# esp_garden.net
KiCad netlist of a schematic drawn in EAGLE
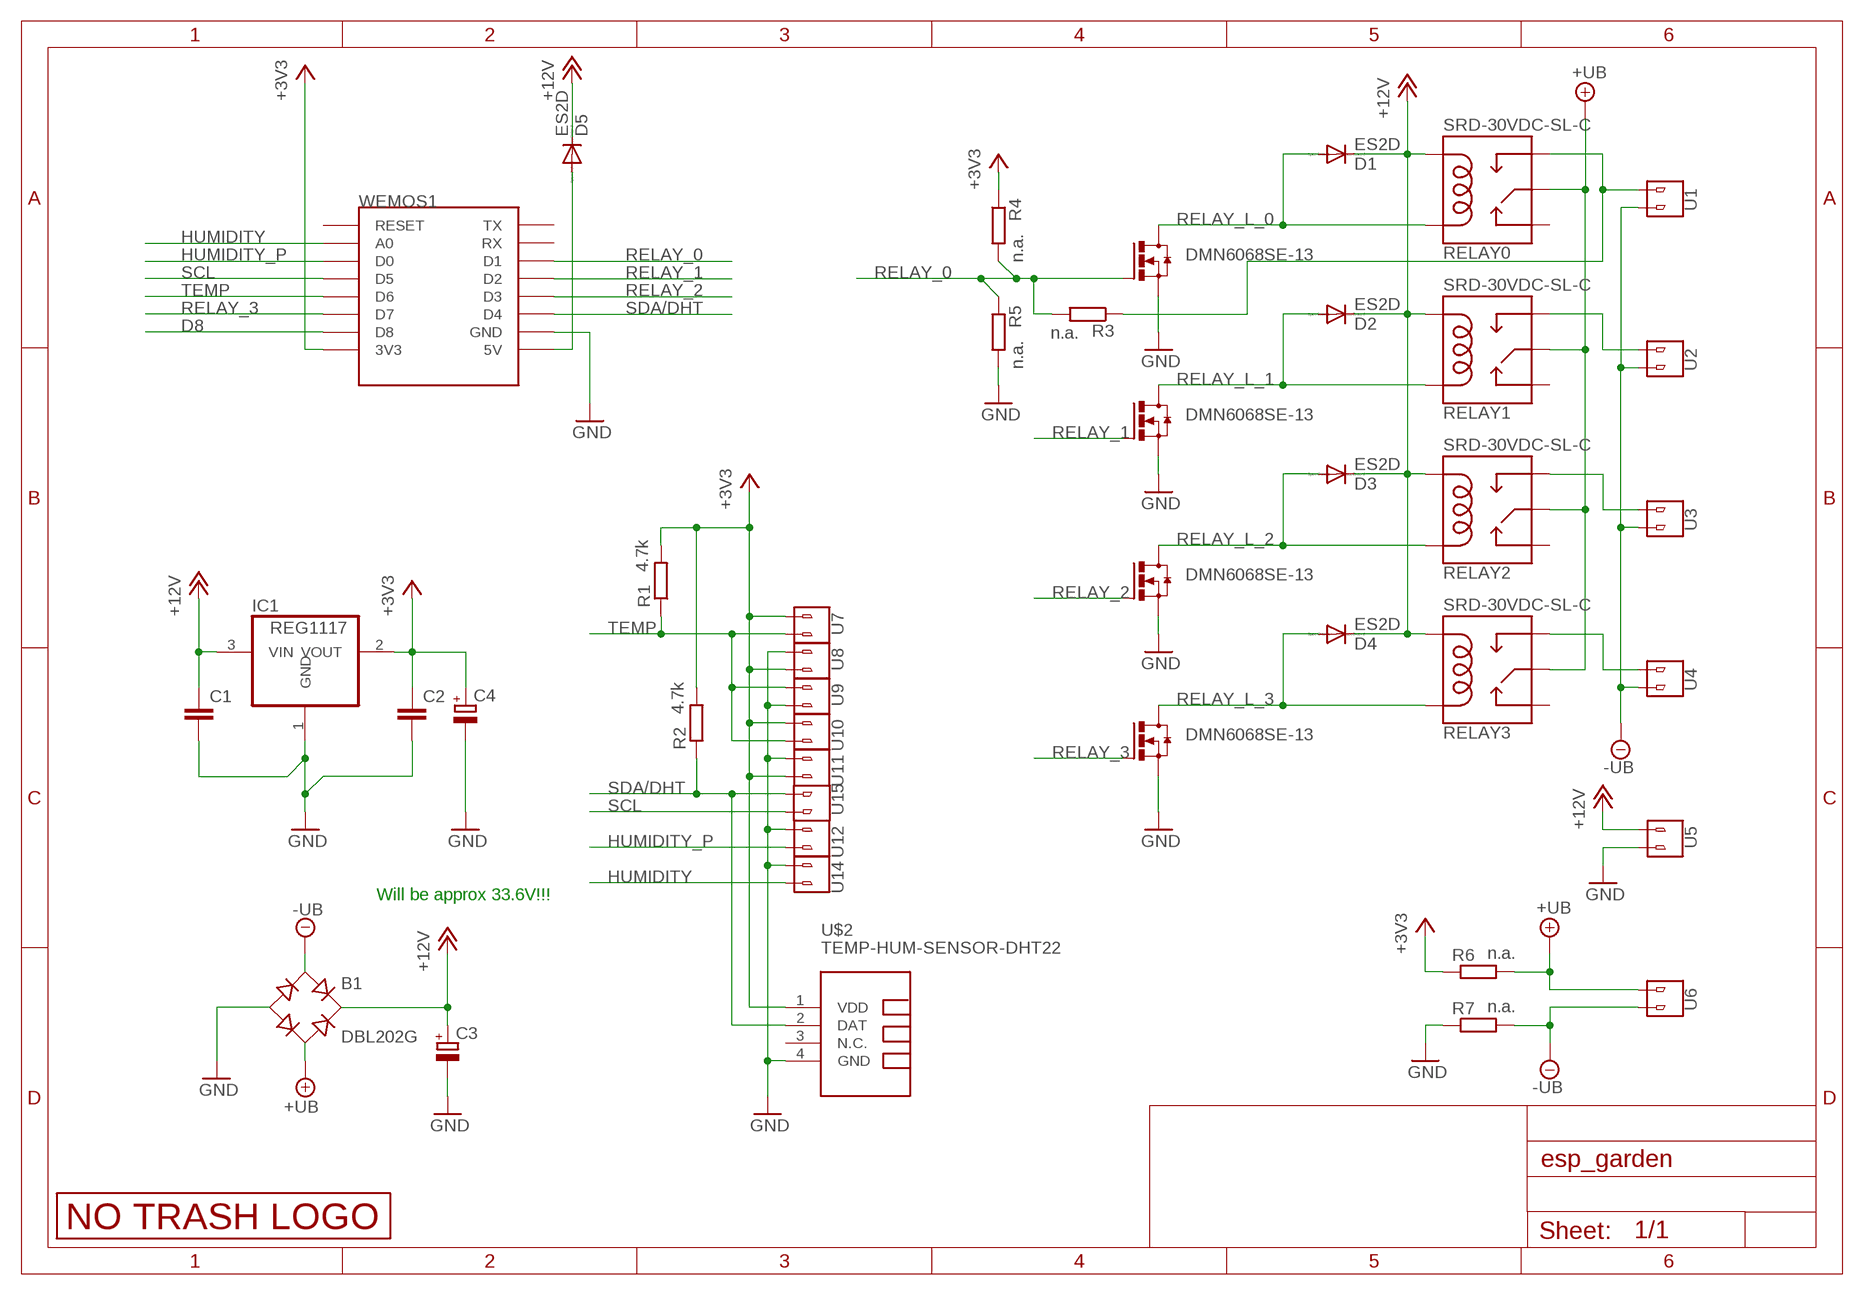
[diagram p0: schematic, sheet 1]

(export (version "E")
  (design (tool "Eeschema 10.0.6"))
  (components
    (comp (ref "B1")
      (value "DBL202G")
      (footprint "eagle-import:DB")
      (libsource (lib "eagle-import") (part "DB?GL202"))
    )
    (comp (ref "C1")
      (value "C-EUC0805")
      (footprint "eagle-import:C0805")
      (libsource (lib "eagle-import") (part "C-EUC0805"))
    )
    (comp (ref "C2")
      (value "C-EUC0805")
      (footprint "eagle-import:C0805")
      (libsource (lib "eagle-import") (part "C-EUC0805"))
    )
    (comp (ref "C3")
      (value "CPOL-EU150CLZ-0810")
      (footprint "eagle-import:150CLZ-0810")
      (libsource (lib "eagle-import") (part "CPOL-EU150CLZ-0810"))
    )
    (comp (ref "C4")
      (value "CPOL-EU150CLZ-0810")
      (footprint "eagle-import:150CLZ-0810")
      (libsource (lib "eagle-import") (part "CPOL-EU150CLZ-0810"))
    )
    (comp (ref "D1")
      (value "ES2D")
      (footprint "eagle-import:SMB")
      (libsource (lib "eagle-import") (part "DIODE-SMB"))
    )
    (comp (ref "D2")
      (value "ES2D")
      (footprint "eagle-import:SMB")
      (libsource (lib "eagle-import") (part "DIODE-SMB"))
    )
    (comp (ref "D3")
      (value "ES2D")
      (footprint "eagle-import:SMB")
      (libsource (lib "eagle-import") (part "DIODE-SMB"))
    )
    (comp (ref "D4")
      (value "ES2D")
      (footprint "eagle-import:SMB")
      (libsource (lib "eagle-import") (part "DIODE-SMB"))
    )
    (comp (ref "D5")
      (value "ES2D")
      (footprint "eagle-import:SMB")
      (libsource (lib "eagle-import") (part "DIODE-SMB"))
    )
    (comp (ref "IC1")
      (value "REG1117")
      (footprint "eagle-import:SOT223")
      (libsource (lib "eagle-import") (part "REG1117"))
    )
    (comp (ref "R1")
      (value "4.7k")
      (footprint "eagle-import:M0805")
      (libsource (lib "eagle-import") (part "R-EU_M0805"))
    )
    (comp (ref "R2")
      (value "4.7k")
      (footprint "eagle-import:M0805")
      (libsource (lib "eagle-import") (part "R-EU_M0805"))
    )
    (comp (ref "R3")
      (value "n.a.")
      (footprint "eagle-import:M0805")
      (libsource (lib "eagle-import") (part "R-EU_M0805"))
    )
    (comp (ref "R4")
      (value "n.a.")
      (footprint "eagle-import:M0805")
      (libsource (lib "eagle-import") (part "R-EU_M0805"))
    )
    (comp (ref "R5")
      (value "n.a.")
      (footprint "eagle-import:M0805")
      (libsource (lib "eagle-import") (part "R-EU_M0805"))
    )
    (comp (ref "R6")
      (value "n.a.")
      (footprint "eagle-import:M0805")
      (libsource (lib "eagle-import") (part "R-EU_M0805"))
    )
    (comp (ref "R7")
      (value "n.a.")
      (footprint "eagle-import:M0805")
      (libsource (lib "eagle-import") (part "R-EU_M0805"))
    )
    (comp (ref "RELAY0")
      (value "SRD-30VDC-SL-C")
      (footprint "eagle-import:SRD-05VDC-SL-C")
      (libsource (lib "eagle-import") (part "RELAYPTH"))
    )
    (comp (ref "RELAY1")
      (value "SRD-30VDC-SL-C")
      (footprint "eagle-import:SRD-05VDC-SL-C")
      (libsource (lib "eagle-import") (part "RELAYPTH"))
    )
    (comp (ref "RELAY2")
      (value "SRD-30VDC-SL-C")
      (footprint "eagle-import:SRD-05VDC-SL-C")
      (libsource (lib "eagle-import") (part "RELAYPTH"))
    )
    (comp (ref "RELAY3")
      (value "SRD-30VDC-SL-C")
      (footprint "eagle-import:SRD-05VDC-SL-C")
      (libsource (lib "eagle-import") (part "RELAYPTH"))
    )
    (comp (ref "T1")
      (value "DMN6068SE-13")
      (footprint "eagle-import:SOT223")
      (libsource (lib "eagle-import") (part "NMOSFET_SMD_223"))
    )
    (comp (ref "T2")
      (value "DMN6068SE-13")
      (footprint "eagle-import:SOT223")
      (libsource (lib "eagle-import") (part "NMOSFET_SMD_223"))
    )
    (comp (ref "T3")
      (value "DMN6068SE-13")
      (footprint "eagle-import:SOT223")
      (libsource (lib "eagle-import") (part "NMOSFET_SMD_223"))
    )
    (comp (ref "T4")
      (value "DMN6068SE-13")
      (footprint "eagle-import:SOT223")
      (libsource (lib "eagle-import") (part "NMOSFET_SMD_223"))
    )
    (comp (ref "U$1")
      (value "LOGO_NO_TRASHNO_TRASH")
      (footprint "eagle-import:LOGO_ROHS_NO_TRASH")
      (libsource (lib "eagle-import") (part "LOGO_NO_TRASHNO_TRASH"))
    )
    (comp (ref "U$2")
      (value "TEMP-HUM-SENSOR-DHT22")
      (footprint "eagle-import:TEMP-HUM-SENSOR-DHT22")
      (libsource (lib "eagle-import") (part "TEMP-HUM-SENSOR-DHT22"))
    )
    (comp (ref "U1")
      (value "V1")
      (footprint "eagle-import:2_SCREW_PIN")
      (libsource (lib "eagle-import") (part "2_PIN_CONNECTOR"))
    )
    (comp (ref "U2")
      (value "V1")
      (footprint "eagle-import:2_SCREW_PIN")
      (libsource (lib "eagle-import") (part "2_PIN_CONNECTOR"))
    )
    (comp (ref "U3")
      (value "V1")
      (footprint "eagle-import:2_SCREW_PIN")
      (libsource (lib "eagle-import") (part "2_PIN_CONNECTOR"))
    )
    (comp (ref "U4")
      (value "V1")
      (footprint "eagle-import:2_SCREW_PIN")
      (libsource (lib "eagle-import") (part "2_PIN_CONNECTOR"))
    )
    (comp (ref "U5")
      (value "V1")
      (footprint "eagle-import:2_SCREW_PIN")
      (libsource (lib "eagle-import") (part "2_PIN_CONNECTOR"))
    )
    (comp (ref "U6")
      (value "V1")
      (footprint "eagle-import:2_SCREW_PIN")
      (libsource (lib "eagle-import") (part "2_PIN_CONNECTOR"))
    )
    (comp (ref "U7")
      (value "V1")
      (footprint "eagle-import:2_SCREW_PIN")
      (libsource (lib "eagle-import") (part "2_PIN_CONNECTOR"))
    )
    (comp (ref "U8")
      (value "V1")
      (footprint "eagle-import:2_SCREW_PIN")
      (libsource (lib "eagle-import") (part "2_PIN_CONNECTOR"))
    )
    (comp (ref "U9")
      (value "V1")
      (footprint "eagle-import:2_SCREW_PIN")
      (libsource (lib "eagle-import") (part "2_PIN_CONNECTOR"))
    )
    (comp (ref "U10")
      (value "V1")
      (footprint "eagle-import:2_SCREW_PIN")
      (libsource (lib "eagle-import") (part "2_PIN_CONNECTOR"))
    )
    (comp (ref "U11")
      (value "V1")
      (footprint "eagle-import:2_SCREW_PIN")
      (libsource (lib "eagle-import") (part "2_PIN_CONNECTOR"))
    )
    (comp (ref "U12")
      (value "V1")
      (footprint "eagle-import:2_SCREW_PIN")
      (libsource (lib "eagle-import") (part "2_PIN_CONNECTOR"))
    )
    (comp (ref "U14")
      (value "V1")
      (footprint "eagle-import:2_SCREW_PIN")
      (libsource (lib "eagle-import") (part "2_PIN_CONNECTOR"))
    )
    (comp (ref "U15")
      (value "V1")
      (footprint "eagle-import:2_SCREW_PIN")
      (libsource (lib "eagle-import") (part "2_PIN_CONNECTOR"))
    )
    (comp (ref "WEMOS1")
      (value "WEMOS-D1-MINI")
      (footprint "eagle-import:WEMOS-D1-MINI")
      (libsource (lib "eagle-import") (part "WEMOS-D1-MINI"))
    )
  )
  (nets
    (net (code "1") (name "+3V3") (class "Default")
      (node (ref "C2") (pin "1") (pinfunction "1_1") (pintype "passive"))
      (node (ref "C4") (pin "+") (pinfunction "+_+") (pintype "passive"))
      (node (ref "IC1") (pin "2") (pinfunction "VOUT_2") (pintype "output"))
      (node (ref "R1") (pin "2") (pinfunction "2_2") (pintype "passive"))
      (node (ref "R2") (pin "2") (pinfunction "2_2") (pintype "passive"))
      (node (ref "R4") (pin "1") (pinfunction "1_1") (pintype "passive"))
      (node (ref "R6") (pin "1") (pinfunction "1_1") (pintype "passive"))
      (node (ref "U$2") (pin "1") (pinfunction "VDD_1") (pintype "power_in"))
      (node (ref "U10") (pin "P$2") (pinfunction "2_P$2") (pintype "passive"))
      (node (ref "U11") (pin "P$1") (pinfunction "1_P$1") (pintype "passive"))
      (node (ref "U7") (pin "P$2") (pinfunction "2_P$2") (pintype "passive"))
      (node (ref "U8") (pin "P$1") (pinfunction "1_P$1") (pintype "passive"))
      (node (ref "WEMOS1") (pin "3V3") (pinfunction "3V3_3V3") (pintype "bidirectional"))
    )
    (net (code "2") (name "+12V") (class "Default")
      (node (ref "B1") (pin "+") (pinfunction "+_+") (pintype "passive"))
      (node (ref "C1") (pin "1") (pinfunction "1_1") (pintype "passive"))
      (node (ref "C3") (pin "+") (pinfunction "+_+") (pintype "passive"))
      (node (ref "D1") (pin "C") (pinfunction "C_C") (pintype "passive"))
      (node (ref "D2") (pin "C") (pinfunction "C_C") (pintype "passive"))
      (node (ref "D3") (pin "C") (pinfunction "C_C") (pintype "passive"))
      (node (ref "D4") (pin "C") (pinfunction "C_C") (pintype "passive"))
      (node (ref "D5") (pin "C") (pinfunction "C_C") (pintype "passive"))
      (node (ref "IC1") (pin "3") (pinfunction "VIN_3") (pintype "input"))
      (node (ref "RELAY0") (pin "COIL0") (pinfunction "COIL0_COIL0") (pintype "bidirectional"))
      (node (ref "RELAY1") (pin "COIL0") (pinfunction "COIL0_COIL0") (pintype "bidirectional"))
      (node (ref "RELAY2") (pin "COIL0") (pinfunction "COIL0_COIL0") (pintype "bidirectional"))
      (node (ref "RELAY3") (pin "COIL0") (pinfunction "COIL0_COIL0") (pintype "bidirectional"))
      (node (ref "U5") (pin "P$2") (pinfunction "2_P$2") (pintype "passive"))
    )
    (net (code "3") (name "+UB") (class "Default")
      (node (ref "B1") (pin "AC2") (pinfunction "AC2_AC2") (pintype "passive"))
      (node (ref "R6") (pin "2") (pinfunction "2_2") (pintype "passive"))
      (node (ref "RELAY0") (pin "SWCOMMON") (pinfunction "SWCOMMON_SWCOMMON") (pintype "bidirectional"))
      (node (ref "RELAY1") (pin "SWCOMMON") (pinfunction "SWCOMMON_SWCOMMON") (pintype "bidirectional"))
      (node (ref "RELAY2") (pin "SWCOMMON") (pinfunction "SWCOMMON_SWCOMMON") (pintype "bidirectional"))
      (node (ref "RELAY3") (pin "SWCOMMON") (pinfunction "SWCOMMON_SWCOMMON") (pintype "bidirectional"))
      (node (ref "U6") (pin "P$1") (pinfunction "1_P$1") (pintype "passive"))
    )
    (net (code "4") (name "-UB") (class "Default")
      (node (ref "B1") (pin "AC1") (pinfunction "AC1_AC1") (pintype "passive"))
      (node (ref "R7") (pin "2") (pinfunction "2_2") (pintype "passive"))
      (node (ref "U1") (pin "P$2") (pinfunction "2_P$2") (pintype "passive"))
      (node (ref "U2") (pin "P$2") (pinfunction "2_P$2") (pintype "passive"))
      (node (ref "U3") (pin "P$2") (pinfunction "2_P$2") (pintype "passive"))
      (node (ref "U4") (pin "P$2") (pinfunction "2_P$2") (pintype "passive"))
      (node (ref "U6") (pin "P$2") (pinfunction "2_P$2") (pintype "passive"))
    )
    (net (code "5") (name "/D8") (class "Default")
      (node (ref "WEMOS1") (pin "D8") (pinfunction "D8_D8") (pintype "bidirectional"))
    )
    (net (code "6") (name "/HUMIDITY") (class "Default")
      (node (ref "U14") (pin "P$1") (pinfunction "1_P$1") (pintype "passive"))
      (node (ref "WEMOS1") (pin "A0") (pinfunction "A0_A0") (pintype "bidirectional"))
    )
    (net (code "7") (name "/HUMIDITY_P") (class "Default")
      (node (ref "U12") (pin "P$1") (pinfunction "1_P$1") (pintype "passive"))
      (node (ref "WEMOS1") (pin "D0") (pinfunction "D0_D0") (pintype "bidirectional"))
    )
    (net (code "8") (name "/RELAY_0") (class "Default")
      (node (ref "R3") (pin "2") (pinfunction "2_2") (pintype "passive"))
      (node (ref "R4") (pin "2") (pinfunction "2_2") (pintype "passive"))
      (node (ref "R5") (pin "1") (pinfunction "1_1") (pintype "passive"))
      (node (ref "T1") (pin "1") (pinfunction "G_1") (pintype "passive"))
      (node (ref "WEMOS1") (pin "D1") (pinfunction "D1_D1") (pintype "bidirectional"))
    )
    (net (code "9") (name "/RELAY_1") (class "Default")
      (node (ref "T2") (pin "1") (pinfunction "G_1") (pintype "passive"))
      (node (ref "WEMOS1") (pin "D2") (pinfunction "D2_D2") (pintype "bidirectional"))
    )
    (net (code "10") (name "/RELAY_2") (class "Default")
      (node (ref "T3") (pin "1") (pinfunction "G_1") (pintype "passive"))
      (node (ref "WEMOS1") (pin "D3") (pinfunction "D3_D3") (pintype "bidirectional"))
    )
    (net (code "11") (name "/RELAY_3") (class "Default")
      (node (ref "T4") (pin "1") (pinfunction "G_1") (pintype "passive"))
      (node (ref "WEMOS1") (pin "D7") (pinfunction "D7_D7") (pintype "bidirectional"))
    )
    (net (code "12") (name "/RELAY_L_0") (class "Default")
      (node (ref "D1") (pin "A") (pinfunction "A_A") (pintype "passive"))
      (node (ref "RELAY0") (pin "COIL1") (pinfunction "COIL1_COIL1") (pintype "bidirectional"))
      (node (ref "T1") (pin "2") (pinfunction "D_2") (pintype "passive"))
      (node (ref "T1") (pin "4") (pinfunction "D_4") (pintype "passive"))
    )
    (net (code "13") (name "/RELAY_L_1") (class "Default")
      (node (ref "D2") (pin "A") (pinfunction "A_A") (pintype "passive"))
      (node (ref "RELAY1") (pin "COIL1") (pinfunction "COIL1_COIL1") (pintype "bidirectional"))
      (node (ref "T2") (pin "2") (pinfunction "D_2") (pintype "passive"))
      (node (ref "T2") (pin "4") (pinfunction "D_4") (pintype "passive"))
    )
    (net (code "14") (name "/RELAY_L_2") (class "Default")
      (node (ref "D3") (pin "A") (pinfunction "A_A") (pintype "passive"))
      (node (ref "RELAY2") (pin "COIL1") (pinfunction "COIL1_COIL1") (pintype "bidirectional"))
      (node (ref "T3") (pin "2") (pinfunction "D_2") (pintype "passive"))
      (node (ref "T3") (pin "4") (pinfunction "D_4") (pintype "passive"))
    )
    (net (code "15") (name "/RELAY_L_3") (class "Default")
      (node (ref "D4") (pin "A") (pinfunction "A_A") (pintype "passive"))
      (node (ref "RELAY3") (pin "COIL1") (pinfunction "COIL1_COIL1") (pintype "bidirectional"))
      (node (ref "T4") (pin "2") (pinfunction "D_2") (pintype "passive"))
      (node (ref "T4") (pin "4") (pinfunction "D_4") (pintype "passive"))
    )
    (net (code "16") (name "/SCL") (class "Default")
      (node (ref "U15") (pin "P$2") (pinfunction "2_P$2") (pintype "passive"))
      (node (ref "WEMOS1") (pin "D5") (pinfunction "D5_D5") (pintype "bidirectional"))
    )
    (net (code "17") (name "/SDA{slash}DHT") (class "Default")
      (node (ref "R2") (pin "1") (pinfunction "1_1") (pintype "passive"))
      (node (ref "U$2") (pin "2") (pinfunction "DAT_2") (pintype "bidirectional"))
      (node (ref "U15") (pin "P$1") (pinfunction "1_P$1") (pintype "passive"))
      (node (ref "WEMOS1") (pin "D4") (pinfunction "D4_D4") (pintype "bidirectional"))
    )
    (net (code "18") (name "/TEMP") (class "Default")
      (node (ref "R1") (pin "1") (pinfunction "1_1") (pintype "passive"))
      (node (ref "U10") (pin "P$1") (pinfunction "1_P$1") (pintype "passive"))
      (node (ref "U7") (pin "P$1") (pinfunction "1_P$1") (pintype "passive"))
      (node (ref "U9") (pin "P$2") (pinfunction "2_P$2") (pintype "passive"))
      (node (ref "WEMOS1") (pin "D6") (pinfunction "D6_D6") (pintype "bidirectional"))
    )
    (net (code "19") (name "GND") (class "Default")
      (node (ref "B1") (pin "-") (pinfunction "-_-") (pintype "passive"))
      (node (ref "C1") (pin "2") (pinfunction "2_2") (pintype "passive"))
      (node (ref "C2") (pin "2") (pinfunction "2_2") (pintype "passive"))
      (node (ref "C3") (pin "-") (pinfunction "-_-") (pintype "passive"))
      (node (ref "C4") (pin "-") (pinfunction "-_-") (pintype "passive"))
      (node (ref "IC1") (pin "1") (pinfunction "GND_1") (pintype "power_in"))
      (node (ref "R5") (pin "2") (pinfunction "2_2") (pintype "passive"))
      (node (ref "R7") (pin "1") (pinfunction "1_1") (pintype "passive"))
      (node (ref "T1") (pin "3") (pinfunction "S_3") (pintype "passive"))
      (node (ref "T2") (pin "3") (pinfunction "S_3") (pintype "passive"))
      (node (ref "T3") (pin "3") (pinfunction "S_3") (pintype "passive"))
      (node (ref "T4") (pin "3") (pinfunction "S_3") (pintype "passive"))
      (node (ref "U$2") (pin "4") (pinfunction "GND_4") (pintype "power_in"))
      (node (ref "U11") (pin "P$2") (pinfunction "2_P$2") (pintype "passive"))
      (node (ref "U12") (pin "P$2") (pinfunction "2_P$2") (pintype "passive"))
      (node (ref "U14") (pin "P$2") (pinfunction "2_P$2") (pintype "passive"))
      (node (ref "U5") (pin "P$1") (pinfunction "1_P$1") (pintype "passive"))
      (node (ref "U8") (pin "P$2") (pinfunction "2_P$2") (pintype "passive"))
      (node (ref "U9") (pin "P$1") (pinfunction "1_P$1") (pintype "passive"))
      (node (ref "WEMOS1") (pin "GND") (pinfunction "GND_GND") (pintype "bidirectional"))
    )
    (net (code "20") (name "Net-(D5-PadA)") (class "Default")
      (node (ref "D5") (pin "A") (pinfunction "A_A") (pintype "passive"))
      (node (ref "WEMOS1") (pin "5V") (pinfunction "5V_5V") (pintype "bidirectional"))
    )
    (net (code "21") (name "Net-(U1-1)") (class "Default")
      (node (ref "R3") (pin "1") (pinfunction "1_1") (pintype "passive"))
      (node (ref "RELAY0") (pin "SWOPEN") (pinfunction "SWOPEN_SWOPEN") (pintype "bidirectional"))
      (node (ref "U1") (pin "P$1") (pinfunction "1_P$1") (pintype "passive"))
    )
    (net (code "22") (name "Net-(U2-1)") (class "Default")
      (node (ref "RELAY1") (pin "SWOPEN") (pinfunction "SWOPEN_SWOPEN") (pintype "bidirectional"))
      (node (ref "U2") (pin "P$1") (pinfunction "1_P$1") (pintype "passive"))
    )
    (net (code "23") (name "Net-(U3-1)") (class "Default")
      (node (ref "RELAY2") (pin "SWOPEN") (pinfunction "SWOPEN_SWOPEN") (pintype "bidirectional"))
      (node (ref "U3") (pin "P$1") (pinfunction "1_P$1") (pintype "passive"))
    )
    (net (code "24") (name "Net-(U4-1)") (class "Default")
      (node (ref "RELAY3") (pin "SWOPEN") (pinfunction "SWOPEN_SWOPEN") (pintype "bidirectional"))
      (node (ref "U4") (pin "P$1") (pinfunction "1_P$1") (pintype "passive"))
    )
    (net (code "25") (name "unconnected-(RELAY0-SWCLOSE-PadSWCLOSED)") (class "Default")
      (node (ref "RELAY0") (pin "SWCLOSED") (pinfunction "SWCLOSE_SWCLOSED") (pintype "bidirectional"))
    )
    (net (code "26") (name "unconnected-(RELAY1-SWCLOSE-PadSWCLOSED)") (class "Default")
      (node (ref "RELAY1") (pin "SWCLOSED") (pinfunction "SWCLOSE_SWCLOSED") (pintype "bidirectional"))
    )
    (net (code "27") (name "unconnected-(RELAY2-SWCLOSE-PadSWCLOSED)") (class "Default")
      (node (ref "RELAY2") (pin "SWCLOSED") (pinfunction "SWCLOSE_SWCLOSED") (pintype "bidirectional"))
    )
    (net (code "28") (name "unconnected-(RELAY3-SWCLOSE-PadSWCLOSED)") (class "Default")
      (node (ref "RELAY3") (pin "SWCLOSED") (pinfunction "SWCLOSE_SWCLOSED") (pintype "bidirectional"))
    )
    (net (code "29") (name "unconnected-(U$2-N.C.-Pad3)") (class "Default")
      (node (ref "U$2") (pin "3") (pinfunction "N.C._3") (pintype "passive"))
    )
    (net (code "30") (name "unconnected-(WEMOS1-PadRESET)") (class "Default")
      (node (ref "WEMOS1") (pin "RESET") (pinfunction "RESET_RESET") (pintype "bidirectional"))
    )
    (net (code "31") (name "unconnected-(WEMOS1-PadRX)") (class "Default")
      (node (ref "WEMOS1") (pin "RX") (pinfunction "RX_RX") (pintype "bidirectional"))
    )
    (net (code "32") (name "unconnected-(WEMOS1-PadTX)") (class "Default")
      (node (ref "WEMOS1") (pin "TX") (pinfunction "TX_TX") (pintype "bidirectional"))
    )
  )
)
